# PCA9548A_QT_Schematic.net
KiCad netlist of a schematic drawn in EAGLE
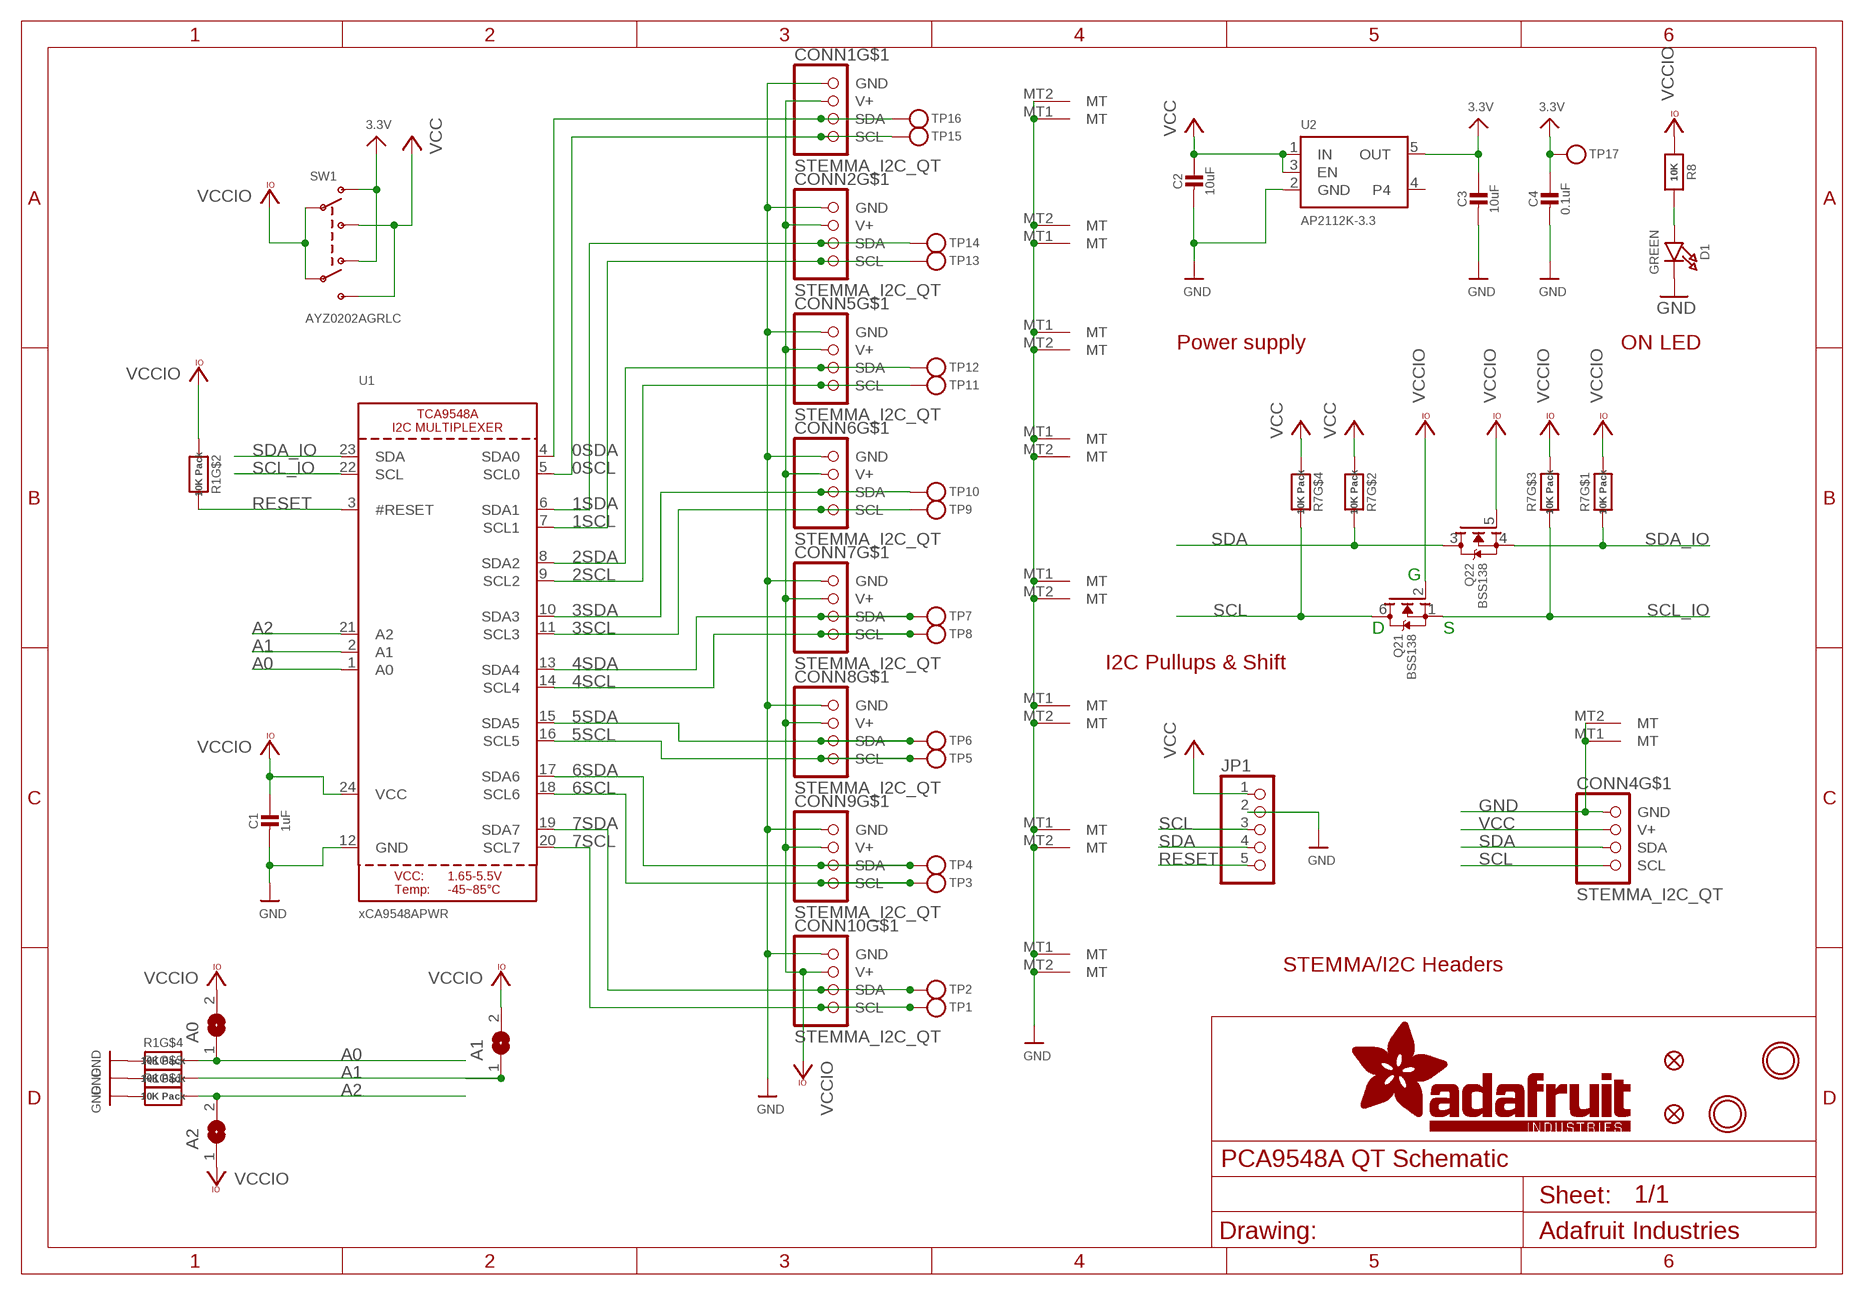
[diagram p0: schematic, sheet 1]

(export (version "E")
  (design (tool "Eeschema 10.0.6"))
  (components
    (comp (ref "A0")
      (value "SOLDERJUMPER")
      (footprint "eagle-import:SOLDERJUMPER_ARROW_NOPASTE")
      (libsource (lib "eagle-import") (part "SOLDERJUMPER"))
    )
    (comp (ref "A1")
      (value "SOLDERJUMPER")
      (footprint "eagle-import:SOLDERJUMPER_ARROW_NOPASTE")
      (libsource (lib "eagle-import") (part "SOLDERJUMPER"))
    )
    (comp (ref "A2")
      (value "SOLDERJUMPER")
      (footprint "eagle-import:SOLDERJUMPER_ARROW_NOPASTE")
      (libsource (lib "eagle-import") (part "SOLDERJUMPER"))
    )
    (comp (ref "C1")
      (value "1uF")
      (footprint "eagle-import:0603-NO")
      (libsource (lib "eagle-import") (part "CAP_CERAMIC0603_NO"))
    )
    (comp (ref "C2")
      (value "10uF")
      (footprint "eagle-import:0805-NO")
      (libsource (lib "eagle-import") (part "CAP_CERAMIC0805-NOOUTLINE"))
    )
    (comp (ref "C3")
      (value "10uF")
      (footprint "eagle-import:0805-NO")
      (libsource (lib "eagle-import") (part "CAP_CERAMIC0805-NOOUTLINE"))
    )
    (comp (ref "C4")
      (value "0.1uF")
      (footprint "eagle-import:0603-NO")
      (libsource (lib "eagle-import") (part "CAP_CERAMIC0603_NO"))
    )
    (comp (ref "CONN1")
      (value "STEMMA_I2C_QT")
      (footprint "eagle-import:JST_SH4")
      (libsource (lib "eagle-import") (part "STEMMA_I2C_QT"))
    )
    (comp (ref "CONN2")
      (value "STEMMA_I2C_QT")
      (footprint "eagle-import:JST_SH4")
      (libsource (lib "eagle-import") (part "STEMMA_I2C_QT"))
    )
    (comp (ref "CONN4")
      (value "STEMMA_I2C_QT")
      (footprint "eagle-import:JST_SH4")
      (libsource (lib "eagle-import") (part "STEMMA_I2C_QT"))
    )
    (comp (ref "CONN5")
      (value "STEMMA_I2C_QT")
      (footprint "eagle-import:JST_SH4")
      (libsource (lib "eagle-import") (part "STEMMA_I2C_QT"))
    )
    (comp (ref "CONN6")
      (value "STEMMA_I2C_QT")
      (footprint "eagle-import:JST_SH4")
      (libsource (lib "eagle-import") (part "STEMMA_I2C_QT"))
    )
    (comp (ref "CONN7")
      (value "STEMMA_I2C_QT")
      (footprint "eagle-import:JST_SH4")
      (libsource (lib "eagle-import") (part "STEMMA_I2C_QT"))
    )
    (comp (ref "CONN8")
      (value "STEMMA_I2C_QT")
      (footprint "eagle-import:JST_SH4")
      (libsource (lib "eagle-import") (part "STEMMA_I2C_QT"))
    )
    (comp (ref "CONN9")
      (value "STEMMA_I2C_QT")
      (footprint "eagle-import:JST_SH4")
      (libsource (lib "eagle-import") (part "STEMMA_I2C_QT"))
    )
    (comp (ref "CONN10")
      (value "STEMMA_I2C_QT")
      (footprint "eagle-import:JST_SH4")
      (libsource (lib "eagle-import") (part "STEMMA_I2C_QT"))
    )
    (comp (ref "D1")
      (value "GREEN")
      (footprint "eagle-import:CHIPLED_0603_NOOUTLINE")
      (libsource (lib "eagle-import") (part "LED0603_NOOUTLINE"))
    )
    (comp (ref "FID2")
      (value "FIDUCIAL_1MM")
      (footprint "eagle-import:FIDUCIAL_1MM")
      (libsource (lib "eagle-import") (part "FIDUCIAL_1MM"))
    )
    (comp (ref "FID4")
      (value "FIDUCIAL_1MM")
      (footprint "eagle-import:FIDUCIAL_1MM")
      (libsource (lib "eagle-import") (part "FIDUCIAL_1MM"))
    )
    (comp (ref "JP1")
      (value "HEADER-1X570MIL")
      (footprint "eagle-import:1X05_ROUND_70")
      (libsource (lib "eagle-import") (part "HEADER-1X570MIL"))
    )
    (comp (ref "Q2")
      (value "BSS138")
      (footprint "eagle-import:SOT363")
      (libsource (lib "eagle-import") (part "MOSFET-N_DUAL"))
    )
    (comp (ref "R1")
      (value "10K Pack")
      (footprint "eagle-import:RESPACK_4X0603")
      (libsource (lib "eagle-import") (part "RESISTOR_4PACK"))
    )
    (comp (ref "R7")
      (value "10K Pack")
      (footprint "eagle-import:RESPACK_4X0603")
      (libsource (lib "eagle-import") (part "RESISTOR_4PACK"))
    )
    (comp (ref "R8")
      (value "10K")
      (footprint "eagle-import:0603-NO")
      (libsource (lib "eagle-import") (part "RESISTOR_0603_NOOUT"))
    )
    (comp (ref "SW1")
      (value "AYZ0202AGRLC")
      (footprint "eagle-import:EG1390")
      (libsource (lib "eagle-import") (part "SWITCH_DPDTEG1390"))
    )
    (comp (ref "TP1")
      (value "TESTPOINTROUND1.5MMNO")
      (footprint "eagle-import:TESTPOINT_ROUND_1.5MM_NO")
      (libsource (lib "eagle-import") (part "TESTPOINTROUND1.5MMNO"))
    )
    (comp (ref "TP2")
      (value "TESTPOINTROUND1.5MMNO")
      (footprint "eagle-import:TESTPOINT_ROUND_1.5MM_NO")
      (libsource (lib "eagle-import") (part "TESTPOINTROUND1.5MMNO"))
    )
    (comp (ref "TP3")
      (value "TESTPOINTROUND1.5MMNO")
      (footprint "eagle-import:TESTPOINT_ROUND_1.5MM_NO")
      (libsource (lib "eagle-import") (part "TESTPOINTROUND1.5MMNO"))
    )
    (comp (ref "TP4")
      (value "TESTPOINTROUND1.5MMNO")
      (footprint "eagle-import:TESTPOINT_ROUND_1.5MM_NO")
      (libsource (lib "eagle-import") (part "TESTPOINTROUND1.5MMNO"))
    )
    (comp (ref "TP5")
      (value "TESTPOINTROUND1.5MMNO")
      (footprint "eagle-import:TESTPOINT_ROUND_1.5MM_NO")
      (libsource (lib "eagle-import") (part "TESTPOINTROUND1.5MMNO"))
    )
    (comp (ref "TP6")
      (value "TESTPOINTROUND1.5MMNO")
      (footprint "eagle-import:TESTPOINT_ROUND_1.5MM_NO")
      (libsource (lib "eagle-import") (part "TESTPOINTROUND1.5MMNO"))
    )
    (comp (ref "TP7")
      (value "TESTPOINTROUND1.5MMNO")
      (footprint "eagle-import:TESTPOINT_ROUND_1.5MM_NO")
      (libsource (lib "eagle-import") (part "TESTPOINTROUND1.5MMNO"))
    )
    (comp (ref "TP8")
      (value "TESTPOINTROUND1.5MMNO")
      (footprint "eagle-import:TESTPOINT_ROUND_1.5MM_NO")
      (libsource (lib "eagle-import") (part "TESTPOINTROUND1.5MMNO"))
    )
    (comp (ref "TP9")
      (value "TESTPOINTROUND1.5MMNO")
      (footprint "eagle-import:TESTPOINT_ROUND_1.5MM_NO")
      (libsource (lib "eagle-import") (part "TESTPOINTROUND1.5MMNO"))
    )
    (comp (ref "TP10")
      (value "TESTPOINTROUND1.5MMNO")
      (footprint "eagle-import:TESTPOINT_ROUND_1.5MM_NO")
      (libsource (lib "eagle-import") (part "TESTPOINTROUND1.5MMNO"))
    )
    (comp (ref "TP11")
      (value "TESTPOINTROUND1.5MMNO")
      (footprint "eagle-import:TESTPOINT_ROUND_1.5MM_NO")
      (libsource (lib "eagle-import") (part "TESTPOINTROUND1.5MMNO"))
    )
    (comp (ref "TP12")
      (value "TESTPOINTROUND1.5MMNO")
      (footprint "eagle-import:TESTPOINT_ROUND_1.5MM_NO")
      (libsource (lib "eagle-import") (part "TESTPOINTROUND1.5MMNO"))
    )
    (comp (ref "TP13")
      (value "TESTPOINTROUND1.5MMNO")
      (footprint "eagle-import:TESTPOINT_ROUND_1.5MM_NO")
      (libsource (lib "eagle-import") (part "TESTPOINTROUND1.5MMNO"))
    )
    (comp (ref "TP14")
      (value "TESTPOINTROUND1.5MMNO")
      (footprint "eagle-import:TESTPOINT_ROUND_1.5MM_NO")
      (libsource (lib "eagle-import") (part "TESTPOINTROUND1.5MMNO"))
    )
    (comp (ref "TP15")
      (value "TESTPOINTROUND1.5MMNO")
      (footprint "eagle-import:TESTPOINT_ROUND_1.5MM_NO")
      (libsource (lib "eagle-import") (part "TESTPOINTROUND1.5MMNO"))
    )
    (comp (ref "TP16")
      (value "TESTPOINTROUND1.5MMNO")
      (footprint "eagle-import:TESTPOINT_ROUND_1.5MM_NO")
      (libsource (lib "eagle-import") (part "TESTPOINTROUND1.5MMNO"))
    )
    (comp (ref "TP17")
      (value "TESTPOINTROUND1.5MMNO")
      (footprint "eagle-import:TESTPOINT_ROUND_1.5MM_NO")
      (libsource (lib "eagle-import") (part "TESTPOINTROUND1.5MMNO"))
    )
    (comp (ref "U$19")
      (value "MOUNTINGHOLE2.5")
      (footprint "eagle-import:MOUNTINGHOLE_2.5_PLATED")
      (libsource (lib "eagle-import") (part "MOUNTINGHOLE2.5"))
    )
    (comp (ref "U$22")
      (value "MOUNTINGHOLE2.5")
      (footprint "eagle-import:MOUNTINGHOLE_2.5_PLATED")
      (libsource (lib "eagle-import") (part "MOUNTINGHOLE2.5"))
    )
    (comp (ref "U1")
      (value "xCA9548APWR")
      (footprint "eagle-import:TSSOP24")
      (libsource (lib "eagle-import") (part "TCA9548A"))
    )
    (comp (ref "U2")
      (value "AP2112K-3.3")
      (footprint "eagle-import:SOT23-5")
      (fields (field (name "JLC_ROTATION") "0"))
      (libsource (lib "eagle-import") (part "VREG_SOT23-5"))
    )
  )
  (nets
    (net (code "1") (name "/0SCL") (class "Default")
      (node (ref "CONN1") (pin "4") (pinfunction "SCL_4") (pintype "passive"))
      (node (ref "TP15") (pin "P$1") (pinfunction "P$1_P$1") (pintype "bidirectional"))
      (node (ref "U1") (pin "5") (pinfunction "SCL0_5") (pintype "bidirectional"))
    )
    (net (code "2") (name "/0SDA") (class "Default")
      (node (ref "CONN1") (pin "3") (pinfunction "SDA_3") (pintype "passive"))
      (node (ref "TP16") (pin "P$1") (pinfunction "P$1_P$1") (pintype "bidirectional"))
      (node (ref "U1") (pin "4") (pinfunction "SDA0_4") (pintype "bidirectional"))
    )
    (net (code "3") (name "/1SCL") (class "Default")
      (node (ref "CONN2") (pin "4") (pinfunction "SCL_4") (pintype "passive"))
      (node (ref "TP13") (pin "P$1") (pinfunction "P$1_P$1") (pintype "bidirectional"))
      (node (ref "U1") (pin "7") (pinfunction "SCL1_7") (pintype "bidirectional"))
    )
    (net (code "4") (name "/1SDA") (class "Default")
      (node (ref "CONN2") (pin "3") (pinfunction "SDA_3") (pintype "passive"))
      (node (ref "TP14") (pin "P$1") (pinfunction "P$1_P$1") (pintype "bidirectional"))
      (node (ref "U1") (pin "6") (pinfunction "SDA1_6") (pintype "bidirectional"))
    )
    (net (code "5") (name "/2SCL") (class "Default")
      (node (ref "CONN5") (pin "4") (pinfunction "SCL_4") (pintype "passive"))
      (node (ref "TP11") (pin "P$1") (pinfunction "P$1_P$1") (pintype "bidirectional"))
      (node (ref "U1") (pin "9") (pinfunction "SCL2_9") (pintype "bidirectional"))
    )
    (net (code "6") (name "/2SDA") (class "Default")
      (node (ref "CONN5") (pin "3") (pinfunction "SDA_3") (pintype "passive"))
      (node (ref "TP12") (pin "P$1") (pinfunction "P$1_P$1") (pintype "bidirectional"))
      (node (ref "U1") (pin "8") (pinfunction "SDA2_8") (pintype "bidirectional"))
    )
    (net (code "7") (name "/3SCL") (class "Default")
      (node (ref "CONN6") (pin "4") (pinfunction "SCL_4") (pintype "passive"))
      (node (ref "TP9") (pin "P$1") (pinfunction "P$1_P$1") (pintype "bidirectional"))
      (node (ref "U1") (pin "11") (pinfunction "SCL3_11") (pintype "bidirectional"))
    )
    (net (code "8") (name "/3SDA") (class "Default")
      (node (ref "CONN6") (pin "3") (pinfunction "SDA_3") (pintype "passive"))
      (node (ref "TP10") (pin "P$1") (pinfunction "P$1_P$1") (pintype "bidirectional"))
      (node (ref "U1") (pin "10") (pinfunction "SDA3_10") (pintype "bidirectional"))
    )
    (net (code "9") (name "/4SCL") (class "Default")
      (node (ref "CONN7") (pin "4") (pinfunction "SCL_4") (pintype "passive"))
      (node (ref "TP8") (pin "P$1") (pinfunction "P$1_P$1") (pintype "bidirectional"))
      (node (ref "U1") (pin "14") (pinfunction "SCL4_14") (pintype "bidirectional"))
    )
    (net (code "10") (name "/4SDA") (class "Default")
      (node (ref "CONN7") (pin "3") (pinfunction "SDA_3") (pintype "passive"))
      (node (ref "TP7") (pin "P$1") (pinfunction "P$1_P$1") (pintype "bidirectional"))
      (node (ref "U1") (pin "13") (pinfunction "SDA4_13") (pintype "bidirectional"))
    )
    (net (code "11") (name "/5SCL") (class "Default")
      (node (ref "CONN8") (pin "4") (pinfunction "SCL_4") (pintype "passive"))
      (node (ref "TP5") (pin "P$1") (pinfunction "P$1_P$1") (pintype "bidirectional"))
      (node (ref "U1") (pin "16") (pinfunction "SCL5_16") (pintype "bidirectional"))
    )
    (net (code "12") (name "/5SDA") (class "Default")
      (node (ref "CONN8") (pin "3") (pinfunction "SDA_3") (pintype "passive"))
      (node (ref "TP6") (pin "P$1") (pinfunction "P$1_P$1") (pintype "bidirectional"))
      (node (ref "U1") (pin "15") (pinfunction "SDA5_15") (pintype "bidirectional"))
    )
    (net (code "13") (name "/6SCL") (class "Default")
      (node (ref "CONN9") (pin "4") (pinfunction "SCL_4") (pintype "passive"))
      (node (ref "TP3") (pin "P$1") (pinfunction "P$1_P$1") (pintype "bidirectional"))
      (node (ref "U1") (pin "18") (pinfunction "SCL6_18") (pintype "bidirectional"))
    )
    (net (code "14") (name "/6SDA") (class "Default")
      (node (ref "CONN9") (pin "3") (pinfunction "SDA_3") (pintype "passive"))
      (node (ref "TP4") (pin "P$1") (pinfunction "P$1_P$1") (pintype "bidirectional"))
      (node (ref "U1") (pin "17") (pinfunction "SDA6_17") (pintype "bidirectional"))
    )
    (net (code "15") (name "/7SCL") (class "Default")
      (node (ref "CONN10") (pin "4") (pinfunction "SCL_4") (pintype "passive"))
      (node (ref "TP1") (pin "P$1") (pinfunction "P$1_P$1") (pintype "bidirectional"))
      (node (ref "U1") (pin "20") (pinfunction "SCL7_20") (pintype "bidirectional"))
    )
    (net (code "16") (name "/7SDA") (class "Default")
      (node (ref "CONN10") (pin "3") (pinfunction "SDA_3") (pintype "passive"))
      (node (ref "TP2") (pin "P$1") (pinfunction "P$1_P$1") (pintype "bidirectional"))
      (node (ref "U1") (pin "19") (pinfunction "SDA7_19") (pintype "bidirectional"))
    )
    (net (code "17") (name "/A0") (class "Default")
      (node (ref "A0") (pin "1") (pinfunction "1_1") (pintype "passive"))
      (node (ref "R1") (pin "5") (pinfunction "2_5") (pintype "passive"))
      (node (ref "U1") (pin "1") (pinfunction "A0_1") (pintype "bidirectional"))
    )
    (net (code "18") (name "/A1") (class "Default")
      (node (ref "A1") (pin "1") (pinfunction "1_1") (pintype "passive"))
      (node (ref "R1") (pin "6") (pinfunction "2_6") (pintype "passive"))
      (node (ref "U1") (pin "2") (pinfunction "A1_2") (pintype "bidirectional"))
    )
    (net (code "19") (name "/A2") (class "Default")
      (node (ref "A2") (pin "2") (pinfunction "2_2") (pintype "passive"))
      (node (ref "R1") (pin "8") (pinfunction "2_8") (pintype "passive"))
      (node (ref "U1") (pin "21") (pinfunction "A2_21") (pintype "bidirectional"))
    )
    (net (code "20") (name "/RESET") (class "Default")
      (node (ref "JP1") (pin "5") (pinfunction "5_5") (pintype "passive"))
      (node (ref "R1") (pin "7") (pinfunction "2_7") (pintype "passive"))
      (node (ref "U1") (pin "3") (pinfunction "#RESET_3") (pintype "bidirectional"))
    )
    (net (code "21") (name "/SCL") (class "Default")
      (node (ref "CONN4") (pin "4") (pinfunction "SCL_4") (pintype "passive"))
      (node (ref "JP1") (pin "3") (pinfunction "3_3") (pintype "passive"))
      (node (ref "Q2") (pin "6") (pinfunction "D_6") (pintype "bidirectional"))
      (node (ref "R7") (pin "5") (pinfunction "2_5") (pintype "passive"))
    )
    (net (code "22") (name "/SCL_IO") (class "Default")
      (node (ref "Q2") (pin "1") (pinfunction "S_1") (pintype "bidirectional"))
      (node (ref "R7") (pin "6") (pinfunction "2_6") (pintype "passive"))
      (node (ref "U1") (pin "22") (pinfunction "SCL_22") (pintype "bidirectional"))
    )
    (net (code "23") (name "/SDA") (class "Default")
      (node (ref "CONN4") (pin "3") (pinfunction "SDA_3") (pintype "passive"))
      (node (ref "JP1") (pin "4") (pinfunction "4_4") (pintype "passive"))
      (node (ref "Q2") (pin "3") (pinfunction "D_3") (pintype "bidirectional"))
      (node (ref "R7") (pin "7") (pinfunction "2_7") (pintype "passive"))
    )
    (net (code "24") (name "/SDA_IO") (class "Default")
      (node (ref "Q2") (pin "4") (pinfunction "S_4") (pintype "bidirectional"))
      (node (ref "R7") (pin "8") (pinfunction "2_8") (pintype "passive"))
      (node (ref "U1") (pin "23") (pinfunction "SDA_23") (pintype "bidirectional"))
    )
    (net (code "25") (name "3.3V") (class "Default")
      (node (ref "C3") (pin "1") (pinfunction "1_1") (pintype "passive"))
      (node (ref "C4") (pin "1") (pinfunction "1_1") (pintype "passive"))
      (node (ref "SW1") (pin "O1") (pinfunction "O1_O1") (pintype "passive"))
      (node (ref "SW1") (pin "O2") (pinfunction "O2_O2") (pintype "passive"))
      (node (ref "TP17") (pin "P$1") (pinfunction "P$1_P$1") (pintype "bidirectional"))
      (node (ref "U2") (pin "5") (pinfunction "OUT_5") (pintype "power_in"))
    )
    (net (code "26") (name "GND") (class "Default")
      (node (ref "C1") (pin "2") (pinfunction "2_2") (pintype "passive"))
      (node (ref "C2") (pin "2") (pinfunction "2_2") (pintype "passive"))
      (node (ref "C3") (pin "2") (pinfunction "2_2") (pintype "passive"))
      (node (ref "C4") (pin "2") (pinfunction "2_2") (pintype "passive"))
      (node (ref "CONN1") (pin "1") (pinfunction "GND_1") (pintype "passive"))
      (node (ref "CONN1") (pin "MT1") (pinfunction "MT_MT1") (pintype "bidirectional"))
      (node (ref "CONN1") (pin "MT2") (pinfunction "MT_MT2") (pintype "bidirectional"))
      (node (ref "CONN10") (pin "1") (pinfunction "GND_1") (pintype "passive"))
      (node (ref "CONN10") (pin "MT1") (pinfunction "MT_MT1") (pintype "bidirectional"))
      (node (ref "CONN10") (pin "MT2") (pinfunction "MT_MT2") (pintype "bidirectional"))
      (node (ref "CONN2") (pin "1") (pinfunction "GND_1") (pintype "passive"))
      (node (ref "CONN2") (pin "MT1") (pinfunction "MT_MT1") (pintype "bidirectional"))
      (node (ref "CONN2") (pin "MT2") (pinfunction "MT_MT2") (pintype "bidirectional"))
      (node (ref "CONN4") (pin "1") (pinfunction "GND_1") (pintype "passive"))
      (node (ref "CONN4") (pin "MT1") (pinfunction "MT_MT1") (pintype "bidirectional"))
      (node (ref "CONN4") (pin "MT2") (pinfunction "MT_MT2") (pintype "bidirectional"))
      (node (ref "CONN5") (pin "1") (pinfunction "GND_1") (pintype "passive"))
      (node (ref "CONN5") (pin "MT1") (pinfunction "MT_MT1") (pintype "bidirectional"))
      (node (ref "CONN5") (pin "MT2") (pinfunction "MT_MT2") (pintype "bidirectional"))
      (node (ref "CONN6") (pin "1") (pinfunction "GND_1") (pintype "passive"))
      (node (ref "CONN6") (pin "MT1") (pinfunction "MT_MT1") (pintype "bidirectional"))
      (node (ref "CONN6") (pin "MT2") (pinfunction "MT_MT2") (pintype "bidirectional"))
      (node (ref "CONN7") (pin "1") (pinfunction "GND_1") (pintype "passive"))
      (node (ref "CONN7") (pin "MT1") (pinfunction "MT_MT1") (pintype "bidirectional"))
      (node (ref "CONN7") (pin "MT2") (pinfunction "MT_MT2") (pintype "bidirectional"))
      (node (ref "CONN8") (pin "1") (pinfunction "GND_1") (pintype "passive"))
      (node (ref "CONN8") (pin "MT1") (pinfunction "MT_MT1") (pintype "bidirectional"))
      (node (ref "CONN8") (pin "MT2") (pinfunction "MT_MT2") (pintype "bidirectional"))
      (node (ref "CONN9") (pin "1") (pinfunction "GND_1") (pintype "passive"))
      (node (ref "CONN9") (pin "MT1") (pinfunction "MT_MT1") (pintype "bidirectional"))
      (node (ref "CONN9") (pin "MT2") (pinfunction "MT_MT2") (pintype "bidirectional"))
      (node (ref "D1") (pin "C") (pinfunction "C_C") (pintype "passive"))
      (node (ref "JP1") (pin "2") (pinfunction "2_2") (pintype "passive"))
      (node (ref "R1") (pin "1") (pinfunction "1_1") (pintype "passive"))
      (node (ref "R1") (pin "3") (pinfunction "1_3") (pintype "passive"))
      (node (ref "R1") (pin "4") (pinfunction "1_4") (pintype "passive"))
      (node (ref "U1") (pin "12") (pinfunction "GND_12") (pintype "bidirectional"))
      (node (ref "U2") (pin "2") (pinfunction "GND_2") (pintype "power_in"))
    )
    (net (code "27") (name "Net-(D1-PadA)") (class "Default")
      (node (ref "D1") (pin "A") (pinfunction "A_A") (pintype "passive"))
      (node (ref "R8") (pin "2") (pinfunction "2_2") (pintype "passive"))
    )
    (net (code "28") (name "VCC") (class "Default")
      (node (ref "C2") (pin "1") (pinfunction "1_1") (pintype "passive"))
      (node (ref "CONN4") (pin "2") (pinfunction "V+_2") (pintype "passive"))
      (node (ref "JP1") (pin "1") (pinfunction "1_1") (pintype "passive"))
      (node (ref "R7") (pin "2") (pinfunction "1_2") (pintype "passive"))
      (node (ref "R7") (pin "4") (pinfunction "1_4") (pintype "passive"))
      (node (ref "SW1") (pin "S1") (pinfunction "S1_S1") (pintype "passive"))
      (node (ref "SW1") (pin "S2") (pinfunction "S2_S2") (pintype "passive"))
      (node (ref "U2") (pin "1") (pinfunction "IN_1") (pintype "power_in"))
      (node (ref "U2") (pin "3") (pinfunction "EN_3") (pintype "input"))
    )
    (net (code "29") (name "VCCIO") (class "Default")
      (node (ref "A0") (pin "2") (pinfunction "2_2") (pintype "passive"))
      (node (ref "A1") (pin "2") (pinfunction "2_2") (pintype "passive"))
      (node (ref "A2") (pin "1") (pinfunction "1_1") (pintype "passive"))
      (node (ref "C1") (pin "1") (pinfunction "1_1") (pintype "passive"))
      (node (ref "CONN1") (pin "2") (pinfunction "V+_2") (pintype "passive"))
      (node (ref "CONN10") (pin "2") (pinfunction "V+_2") (pintype "passive"))
      (node (ref "CONN2") (pin "2") (pinfunction "V+_2") (pintype "passive"))
      (node (ref "CONN5") (pin "2") (pinfunction "V+_2") (pintype "passive"))
      (node (ref "CONN6") (pin "2") (pinfunction "V+_2") (pintype "passive"))
      (node (ref "CONN7") (pin "2") (pinfunction "V+_2") (pintype "passive"))
      (node (ref "CONN8") (pin "2") (pinfunction "V+_2") (pintype "passive"))
      (node (ref "CONN9") (pin "2") (pinfunction "V+_2") (pintype "passive"))
      (node (ref "Q2") (pin "2") (pinfunction "G_2") (pintype "bidirectional"))
      (node (ref "Q2") (pin "5") (pinfunction "G_5") (pintype "bidirectional"))
      (node (ref "R1") (pin "2") (pinfunction "1_2") (pintype "passive"))
      (node (ref "R7") (pin "1") (pinfunction "1_1") (pintype "passive"))
      (node (ref "R7") (pin "3") (pinfunction "1_3") (pintype "passive"))
      (node (ref "R8") (pin "1") (pinfunction "1_1") (pintype "passive"))
      (node (ref "SW1") (pin "P1") (pinfunction "P1_P1") (pintype "passive"))
      (node (ref "SW1") (pin "P2") (pinfunction "P2_P2") (pintype "passive"))
      (node (ref "U1") (pin "24") (pinfunction "VCC_24") (pintype "bidirectional"))
    )
    (net (code "30") (name "unconnected-(U2-P4-Pad4)") (class "Default")
      (node (ref "U2") (pin "4") (pinfunction "P4_4") (pintype "bidirectional"))
    )
  )
)
